# AudioMega_Oliver_v101.net
KiCad netlist of a schematic drawn in EAGLE
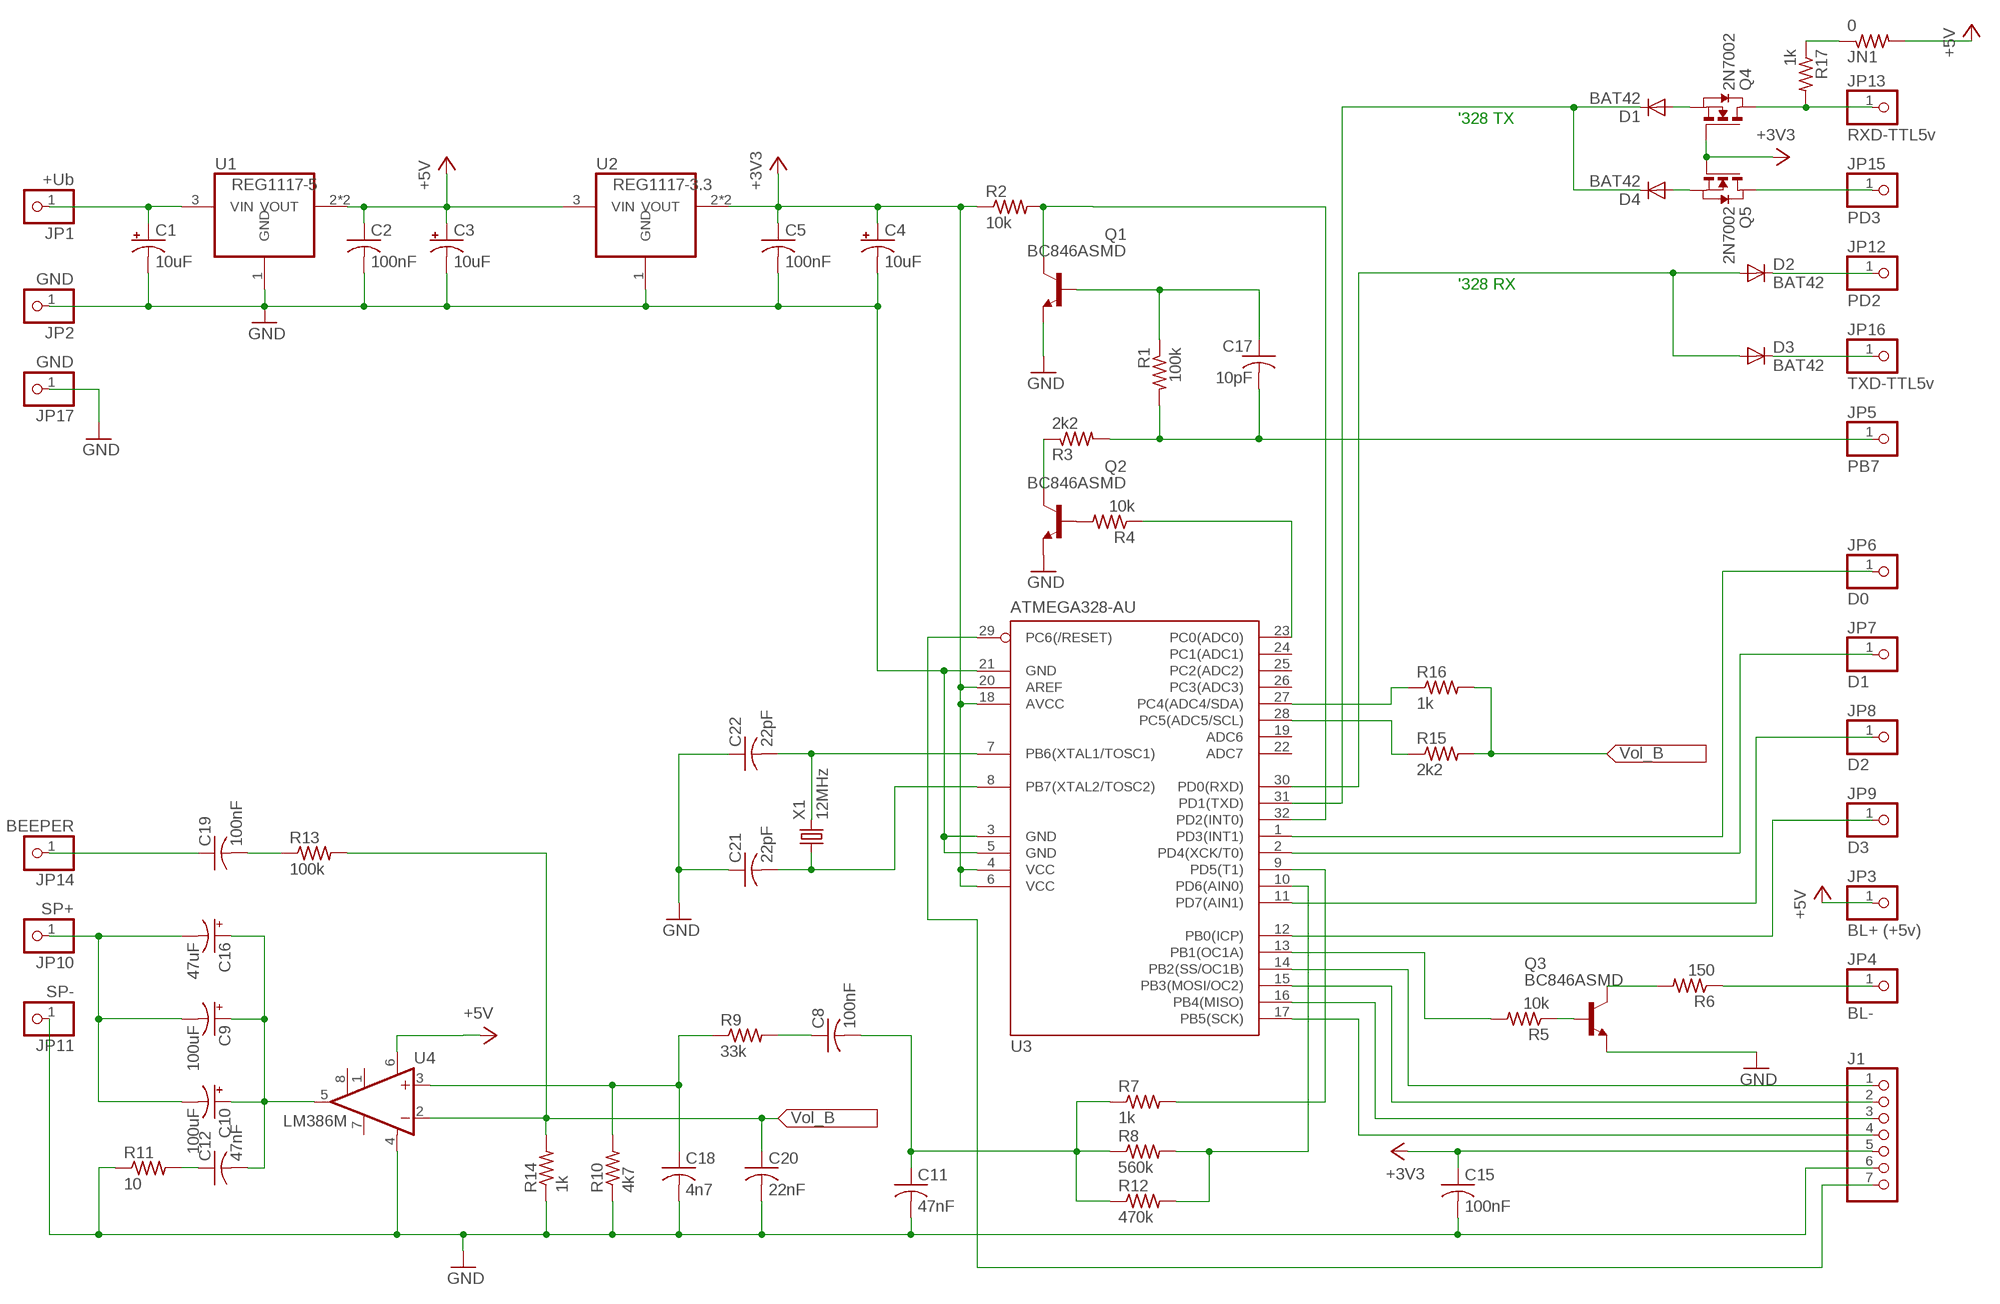
[diagram p0: schematic, sheet 1]

(export (version "E")
  (design (tool "Eeschema 10.0.6"))
  (components
    (comp (ref "C1")
      (value "10uF")
      (footprint "eagle-import:CT3528")
      (libsource (lib "eagle-import") (part "CPOL-USCT3528"))
    )
    (comp (ref "C2")
      (value "100nF")
      (footprint "eagle-import:C1206")
      (libsource (lib "eagle-import") (part "C-USC1206"))
    )
    (comp (ref "C3")
      (value "10uF")
      (footprint "eagle-import:CT3528")
      (libsource (lib "eagle-import") (part "CPOL-USCT3528"))
    )
    (comp (ref "C4")
      (value "10uF")
      (footprint "eagle-import:CT3528")
      (libsource (lib "eagle-import") (part "CPOL-USCT3528"))
    )
    (comp (ref "C5")
      (value "100nF")
      (footprint "eagle-import:C1206")
      (libsource (lib "eagle-import") (part "C-USC1206"))
    )
    (comp (ref "C8")
      (value "100nF")
      (footprint "eagle-import:C1206")
      (libsource (lib "eagle-import") (part "C-USC1206"))
    )
    (comp (ref "C9")
      (value "100uF")
      (footprint "eagle-import:CT6032")
      (libsource (lib "eagle-import") (part "CPOL-USCT6032"))
    )
    (comp (ref "C10")
      (value "100uF")
      (footprint "eagle-import:CT6032")
      (libsource (lib "eagle-import") (part "CPOL-USCT6032"))
    )
    (comp (ref "C11")
      (value "47nF")
      (footprint "eagle-import:C1206")
      (libsource (lib "eagle-import") (part "C-USC1206"))
    )
    (comp (ref "C12")
      (value "47nF")
      (footprint "eagle-import:C1206")
      (libsource (lib "eagle-import") (part "C-USC1206"))
    )
    (comp (ref "C15")
      (value "100nF")
      (footprint "eagle-import:C1206")
      (libsource (lib "eagle-import") (part "C-USC1206"))
    )
    (comp (ref "C16")
      (value "47uF")
      (footprint "eagle-import:CT6032")
      (libsource (lib "eagle-import") (part "CPOL-USCT6032"))
    )
    (comp (ref "C17")
      (value "10pF")
      (footprint "eagle-import:C1206")
      (libsource (lib "eagle-import") (part "C-USC1206"))
    )
    (comp (ref "C18")
      (value "4n7")
      (footprint "eagle-import:C1206")
      (libsource (lib "eagle-import") (part "C-USC1206"))
    )
    (comp (ref "C19")
      (value "100nF")
      (footprint "eagle-import:C1206")
      (libsource (lib "eagle-import") (part "C-USC1206"))
    )
    (comp (ref "C20")
      (value "22nF")
      (footprint "eagle-import:C1206")
      (libsource (lib "eagle-import") (part "C-USC1206"))
    )
    (comp (ref "C21")
      (value "22pF")
      (footprint "eagle-import:C1206")
      (libsource (lib "eagle-import") (part "C-USC1206"))
    )
    (comp (ref "C22")
      (value "22pF")
      (footprint "eagle-import:C1206")
      (libsource (lib "eagle-import") (part "C-USC1206"))
    )
    (comp (ref "D1")
      (value "BAT42")
      (footprint "eagle-import:SOD123")
      (libsource (lib "eagle-import") (part "DIODE-SOD123"))
    )
    (comp (ref "D2")
      (value "BAT42")
      (footprint "eagle-import:SOD123")
      (libsource (lib "eagle-import") (part "DIODE-SOD123"))
    )
    (comp (ref "D3")
      (value "BAT42")
      (footprint "eagle-import:SOD123")
      (libsource (lib "eagle-import") (part "DIODE-SOD123"))
    )
    (comp (ref "D4")
      (value "BAT42")
      (footprint "eagle-import:SOD123")
      (libsource (lib "eagle-import") (part "DIODE-SOD123"))
    )
    (comp (ref "J1")
      (value "PINHD-1X7")
      (footprint "eagle-import:1X07")
      (libsource (lib "eagle-import") (part "PINHD-1X7"))
    )
    (comp (ref "JN1")
      (value "0")
      (footprint "eagle-import:R1206")
      (libsource (lib "eagle-import") (part "R-US_R1206"))
    )
    (comp (ref "JP1")
      (value "+Ub")
      (footprint "eagle-import:1X01")
      (libsource (lib "eagle-import") (part "PINHD-1X1"))
    )
    (comp (ref "JP2")
      (value "GND")
      (footprint "eagle-import:1X01")
      (libsource (lib "eagle-import") (part "PINHD-1X1"))
    )
    (comp (ref "JP3")
      (value "BL+ (+5v)")
      (footprint "eagle-import:1X01")
      (libsource (lib "eagle-import") (part "PINHD-1X1"))
    )
    (comp (ref "JP4")
      (value "BL-")
      (footprint "eagle-import:1X01")
      (libsource (lib "eagle-import") (part "PINHD-1X1"))
    )
    (comp (ref "JP5")
      (value "PB7")
      (footprint "eagle-import:1X01")
      (libsource (lib "eagle-import") (part "PINHD-1X1"))
    )
    (comp (ref "JP6")
      (value "D0")
      (footprint "eagle-import:1X01")
      (libsource (lib "eagle-import") (part "PINHD-1X1"))
    )
    (comp (ref "JP7")
      (value "D1")
      (footprint "eagle-import:1X01")
      (libsource (lib "eagle-import") (part "PINHD-1X1"))
    )
    (comp (ref "JP8")
      (value "D2")
      (footprint "eagle-import:1X01")
      (libsource (lib "eagle-import") (part "PINHD-1X1"))
    )
    (comp (ref "JP9")
      (value "D3")
      (footprint "eagle-import:1X01")
      (libsource (lib "eagle-import") (part "PINHD-1X1"))
    )
    (comp (ref "JP10")
      (value "SP+")
      (footprint "eagle-import:1X01")
      (libsource (lib "eagle-import") (part "PINHD-1X1"))
    )
    (comp (ref "JP11")
      (value "SP-")
      (footprint "eagle-import:1X01")
      (libsource (lib "eagle-import") (part "PINHD-1X1"))
    )
    (comp (ref "JP12")
      (value "PD2")
      (footprint "eagle-import:1X01")
      (libsource (lib "eagle-import") (part "PINHD-1X1"))
    )
    (comp (ref "JP13")
      (value "RXD-TTL5v")
      (footprint "eagle-import:1X01")
      (libsource (lib "eagle-import") (part "PINHD-1X1"))
    )
    (comp (ref "JP14")
      (value "BEEPER")
      (footprint "eagle-import:1X01")
      (libsource (lib "eagle-import") (part "PINHD-1X1"))
    )
    (comp (ref "JP15")
      (value "PD3")
      (footprint "eagle-import:1X01")
      (libsource (lib "eagle-import") (part "PINHD-1X1"))
    )
    (comp (ref "JP16")
      (value "TXD-TTL5v")
      (footprint "eagle-import:1X01")
      (libsource (lib "eagle-import") (part "PINHD-1X1"))
    )
    (comp (ref "JP17")
      (value "GND")
      (footprint "eagle-import:1X01")
      (libsource (lib "eagle-import") (part "PINHD-1X1"))
    )
    (comp (ref "Q1")
      (value "BC846ASMD")
      (footprint "eagle-import:SOT23")
      (libsource (lib "eagle-import") (part "BC846SMDA"))
    )
    (comp (ref "Q2")
      (value "BC846ASMD")
      (footprint "eagle-import:SOT23")
      (libsource (lib "eagle-import") (part "BC846SMDA"))
    )
    (comp (ref "Q3")
      (value "BC846ASMD")
      (footprint "eagle-import:SOT23")
      (libsource (lib "eagle-import") (part "BC846SMDA"))
    )
    (comp (ref "Q4")
      (value "2N7002")
      (footprint "eagle-import:SOT-23")
      (libsource (lib "eagle-import") (part "NMOSSOT23"))
    )
    (comp (ref "Q5")
      (value "2N7002")
      (footprint "eagle-import:SOT-23")
      (fields (field (name "OC_FARNELL") "unknown") (field (name "OC_NEWARK") "unknown"))
      (libsource (lib "eagle-import") (part "NMOSSOT23"))
    )
    (comp (ref "R1")
      (value "100k")
      (footprint "eagle-import:R1206")
      (libsource (lib "eagle-import") (part "R-US_R1206"))
    )
    (comp (ref "R2")
      (value "10k")
      (footprint "eagle-import:R1206")
      (libsource (lib "eagle-import") (part "R-US_R1206"))
    )
    (comp (ref "R3")
      (value "2k2")
      (footprint "eagle-import:R1206")
      (libsource (lib "eagle-import") (part "R-US_R1206"))
    )
    (comp (ref "R4")
      (value "10k")
      (footprint "eagle-import:R1206")
      (libsource (lib "eagle-import") (part "R-US_R1206"))
    )
    (comp (ref "R5")
      (value "10k")
      (footprint "eagle-import:R1206")
      (libsource (lib "eagle-import") (part "R-US_R1206"))
    )
    (comp (ref "R6")
      (value "150")
      (footprint "eagle-import:R1206")
      (libsource (lib "eagle-import") (part "R-US_R1206"))
    )
    (comp (ref "R7")
      (value "1k")
      (footprint "eagle-import:R1206")
      (libsource (lib "eagle-import") (part "R-US_R1206"))
    )
    (comp (ref "R8")
      (value "560k")
      (footprint "eagle-import:R1206")
      (libsource (lib "eagle-import") (part "R-US_R1206"))
    )
    (comp (ref "R9")
      (value "33k")
      (footprint "eagle-import:R1206")
      (libsource (lib "eagle-import") (part "R-US_R1206"))
    )
    (comp (ref "R10")
      (value "4k7")
      (footprint "eagle-import:R1206")
      (libsource (lib "eagle-import") (part "R-US_R1206"))
    )
    (comp (ref "R11")
      (value "10")
      (footprint "eagle-import:R1206")
      (libsource (lib "eagle-import") (part "R-US_R1206"))
    )
    (comp (ref "R12")
      (value "470k")
      (footprint "eagle-import:R1206")
      (libsource (lib "eagle-import") (part "R-US_R1206"))
    )
    (comp (ref "R13")
      (value "100k")
      (footprint "eagle-import:R1206")
      (libsource (lib "eagle-import") (part "R-US_R1206"))
    )
    (comp (ref "R14")
      (value "1k")
      (footprint "eagle-import:R1206")
      (libsource (lib "eagle-import") (part "R-US_R1206"))
    )
    (comp (ref "R15")
      (value "2k2")
      (footprint "eagle-import:R1206")
      (libsource (lib "eagle-import") (part "R-US_R1206"))
    )
    (comp (ref "R16")
      (value "1k")
      (footprint "eagle-import:R1206")
      (libsource (lib "eagle-import") (part "R-US_R1206"))
    )
    (comp (ref "R17")
      (value "1k")
      (footprint "eagle-import:R1206")
      (libsource (lib "eagle-import") (part "R-US_R1206"))
    )
    (comp (ref "U1")
      (value "REG1117-5")
      (footprint "eagle-import:SOT223")
      (fields (field (name "MPN") "REG1117"))
      (libsource (lib "eagle-import") (part "REG1117"))
    )
    (comp (ref "U2")
      (value "REG1117-3.3")
      (footprint "eagle-import:SOT223")
      (fields (field (name "MPN") "REG1117"))
      (libsource (lib "eagle-import") (part "REG1117"))
    )
    (comp (ref "U3")
      (value "ATMEGA328-AU")
      (footprint "eagle-import:TQFP32-08")
      (fields (field (name "MPN") "ATMEGA8-16AU"))
      (libsource (lib "eagle-import") (part "MEGA8-AI"))
    )
    (comp (ref "U4")
      (value "LM386M")
      (footprint "eagle-import:SO08")
      (libsource (lib "eagle-import") (part "LM386?-M1"))
    )
    (comp (ref "X1")
      (value "12MHz")
      (footprint "eagle-import:HC49UP")
      (libsource (lib "eagle-import") (part "CRYSTALHC49UP"))
    )
  )
  (nets
    (net (code "1") (name "+3V3") (class "Default")
      (node (ref "C15") (pin "1") (pinfunction "1_1") (pintype "passive"))
      (node (ref "C4") (pin "+") (pinfunction "+_+") (pintype "passive"))
      (node (ref "C5") (pin "1") (pinfunction "1_1") (pintype "passive"))
      (node (ref "J1") (pin "5") (pinfunction "5_5") (pintype "passive"))
      (node (ref "Q4") (pin "3") (pinfunction "G_3") (pintype "passive"))
      (node (ref "Q5") (pin "3") (pinfunction "G_3") (pintype "passive"))
      (node (ref "R2") (pin "1") (pinfunction "1_1") (pintype "passive"))
      (node (ref "U2") (pin "2") (pinfunction "VOUT_2") (pintype "output"))
      (node (ref "U2") (pin "4") (pinfunction "VOUT_4") (pintype "output"))
      (node (ref "U3") (pin "18") (pinfunction "AVCC_18") (pintype "power_in"))
      (node (ref "U3") (pin "20") (pinfunction "AREF_20") (pintype "passive"))
      (node (ref "U3") (pin "4") (pinfunction "VCC_4") (pintype "power_in"))
      (node (ref "U3") (pin "6") (pinfunction "VCC_6") (pintype "power_in"))
    )
    (net (code "2") (name "+5V") (class "Default")
      (node (ref "C2") (pin "1") (pinfunction "1_1") (pintype "passive"))
      (node (ref "C3") (pin "+") (pinfunction "+_+") (pintype "passive"))
      (node (ref "JN1") (pin "2") (pinfunction "2_2") (pintype "passive"))
      (node (ref "JP3") (pin "1") (pinfunction "1_1") (pintype "passive"))
      (node (ref "U1") (pin "2") (pinfunction "VOUT_2") (pintype "output"))
      (node (ref "U1") (pin "4") (pinfunction "VOUT_4") (pintype "output"))
      (node (ref "U2") (pin "3") (pinfunction "VIN_3") (pintype "input"))
      (node (ref "U4") (pin "6") (pinfunction "VS_6") (pintype "power_in"))
    )
    (net (code "3") (name "/VOL_B") (class "Default")
      (node (ref "C20") (pin "1") (pinfunction "1_1") (pintype "passive"))
      (node (ref "R13") (pin "2") (pinfunction "2_2") (pintype "passive"))
      (node (ref "R14") (pin "2") (pinfunction "2_2") (pintype "passive"))
      (node (ref "R15") (pin "2") (pinfunction "2_2") (pintype "passive"))
      (node (ref "R16") (pin "2") (pinfunction "2_2") (pintype "passive"))
      (node (ref "U4") (pin "2") (pinfunction "-IN_2") (pintype "input"))
    )
    (net (code "4") (name "GND") (class "Default")
      (node (ref "C1") (pin "-") (pinfunction "-_-") (pintype "passive"))
      (node (ref "C11") (pin "2") (pinfunction "2_2") (pintype "passive"))
      (node (ref "C15") (pin "2") (pinfunction "2_2") (pintype "passive"))
      (node (ref "C18") (pin "2") (pinfunction "2_2") (pintype "passive"))
      (node (ref "C2") (pin "2") (pinfunction "2_2") (pintype "passive"))
      (node (ref "C20") (pin "2") (pinfunction "2_2") (pintype "passive"))
      (node (ref "C21") (pin "1") (pinfunction "1_1") (pintype "passive"))
      (node (ref "C22") (pin "1") (pinfunction "1_1") (pintype "passive"))
      (node (ref "C3") (pin "-") (pinfunction "-_-") (pintype "passive"))
      (node (ref "C4") (pin "-") (pinfunction "-_-") (pintype "passive"))
      (node (ref "C5") (pin "2") (pinfunction "2_2") (pintype "passive"))
      (node (ref "J1") (pin "6") (pinfunction "6_6") (pintype "passive"))
      (node (ref "JP11") (pin "1") (pinfunction "1_1") (pintype "passive"))
      (node (ref "JP17") (pin "1") (pinfunction "1_1") (pintype "passive"))
      (node (ref "JP2") (pin "1") (pinfunction "1_1") (pintype "passive"))
      (node (ref "Q1") (pin "2") (pinfunction "E_2") (pintype "passive"))
      (node (ref "Q2") (pin "2") (pinfunction "E_2") (pintype "passive"))
      (node (ref "Q3") (pin "2") (pinfunction "E_2") (pintype "passive"))
      (node (ref "R10") (pin "1") (pinfunction "1_1") (pintype "passive"))
      (node (ref "R11") (pin "1") (pinfunction "1_1") (pintype "passive"))
      (node (ref "R14") (pin "1") (pinfunction "1_1") (pintype "passive"))
      (node (ref "U1") (pin "1") (pinfunction "GND_1") (pintype "power_in"))
      (node (ref "U2") (pin "1") (pinfunction "GND_1") (pintype "power_in"))
      (node (ref "U3") (pin "21") (pinfunction "GND_21") (pintype "power_in"))
      (node (ref "U3") (pin "3") (pinfunction "GND_3") (pintype "power_in"))
      (node (ref "U3") (pin "5") (pinfunction "GND_5") (pintype "power_in"))
      (node (ref "U4") (pin "4") (pinfunction "GND_4") (pintype "power_in"))
    )
    (net (code "5") (name "Net-(C8-Pad1)") (class "Default")
      (node (ref "C8") (pin "1") (pinfunction "1_1") (pintype "passive"))
      (node (ref "R9") (pin "2") (pinfunction "2_2") (pintype "passive"))
    )
    (net (code "6") (name "Net-(C10-Pad-)") (class "Default")
      (node (ref "C10") (pin "-") (pinfunction "-_-") (pintype "passive"))
      (node (ref "C16") (pin "-") (pinfunction "-_-") (pintype "passive"))
      (node (ref "C9") (pin "-") (pinfunction "-_-") (pintype "passive"))
      (node (ref "JP10") (pin "1") (pinfunction "1_1") (pintype "passive"))
    )
    (net (code "7") (name "Net-(C11-Pad1)") (class "Default")
      (node (ref "C11") (pin "1") (pinfunction "1_1") (pintype "passive"))
      (node (ref "C8") (pin "2") (pinfunction "2_2") (pintype "passive"))
      (node (ref "R12") (pin "1") (pinfunction "1_1") (pintype "passive"))
      (node (ref "R7") (pin "1") (pinfunction "1_1") (pintype "passive"))
      (node (ref "R8") (pin "1") (pinfunction "1_1") (pintype "passive"))
    )
    (net (code "8") (name "Net-(C12-Pad1)") (class "Default")
      (node (ref "C12") (pin "1") (pinfunction "1_1") (pintype "passive"))
      (node (ref "R11") (pin "2") (pinfunction "2_2") (pintype "passive"))
    )
    (net (code "9") (name "Net-(C17-Pad2)") (class "Default")
      (node (ref "C17") (pin "2") (pinfunction "2_2") (pintype "passive"))
      (node (ref "JP5") (pin "1") (pinfunction "1_1") (pintype "passive"))
      (node (ref "R1") (pin "2") (pinfunction "2_2") (pintype "passive"))
      (node (ref "R3") (pin "2") (pinfunction "2_2") (pintype "passive"))
    )
    (net (code "10") (name "Net-(C19-Pad1)") (class "Default")
      (node (ref "C19") (pin "1") (pinfunction "1_1") (pintype "passive"))
      (node (ref "JP14") (pin "1") (pinfunction "1_1") (pintype "passive"))
    )
    (net (code "11") (name "Net-(C19-Pad2)") (class "Default")
      (node (ref "C19") (pin "2") (pinfunction "2_2") (pintype "passive"))
      (node (ref "R13") (pin "1") (pinfunction "1_1") (pintype "passive"))
    )
    (net (code "12") (name "Net-(D2-PadC)") (class "Default")
      (node (ref "D2") (pin "C") (pinfunction "C_C") (pintype "passive"))
      (node (ref "JP12") (pin "1") (pinfunction "1_1") (pintype "passive"))
    )
    (net (code "13") (name "Net-(D3-PadC)") (class "Default")
      (node (ref "D3") (pin "C") (pinfunction "C_C") (pintype "passive"))
      (node (ref "JP16") (pin "1") (pinfunction "1_1") (pintype "passive"))
    )
    (net (code "14") (name "Net-(JN1-Pad1)") (class "Default")
      (node (ref "JN1") (pin "1") (pinfunction "1_1") (pintype "passive"))
      (node (ref "R17") (pin "1") (pinfunction "1_1") (pintype "passive"))
    )
    (net (code "15") (name "Net-(JP4-Pad1)") (class "Default")
      (node (ref "JP4") (pin "1") (pinfunction "1_1") (pintype "passive"))
      (node (ref "R6") (pin "1") (pinfunction "1_1") (pintype "passive"))
    )
    (net (code "16") (name "Net-(Q1-B)") (class "Default")
      (node (ref "C17") (pin "1") (pinfunction "1_1") (pintype "passive"))
      (node (ref "Q1") (pin "1") (pinfunction "B_1") (pintype "passive"))
      (node (ref "R1") (pin "1") (pinfunction "1_1") (pintype "passive"))
    )
    (net (code "17") (name "Net-(Q1-C)") (class "Default")
      (node (ref "Q1") (pin "3") (pinfunction "C_3") (pintype "passive"))
      (node (ref "R2") (pin "2") (pinfunction "2_2") (pintype "passive"))
      (node (ref "U3") (pin "32") (pinfunction "PD2(INT0)_32") (pintype "bidirectional"))
    )
    (net (code "18") (name "Net-(Q2-B)") (class "Default")
      (node (ref "Q2") (pin "1") (pinfunction "B_1") (pintype "passive"))
      (node (ref "R4") (pin "2") (pinfunction "2_2") (pintype "passive"))
    )
    (net (code "19") (name "Net-(Q2-C)") (class "Default")
      (node (ref "Q2") (pin "3") (pinfunction "C_3") (pintype "passive"))
      (node (ref "R3") (pin "1") (pinfunction "1_1") (pintype "passive"))
    )
    (net (code "20") (name "Net-(Q3-B)") (class "Default")
      (node (ref "Q3") (pin "1") (pinfunction "B_1") (pintype "passive"))
      (node (ref "R5") (pin "1") (pinfunction "1_1") (pintype "passive"))
    )
    (net (code "21") (name "Net-(Q3-C)") (class "Default")
      (node (ref "Q3") (pin "3") (pinfunction "C_3") (pintype "passive"))
      (node (ref "R6") (pin "2") (pinfunction "2_2") (pintype "passive"))
    )
    (net (code "22") (name "Net-(Q4-D)") (class "Default")
      (node (ref "JP13") (pin "1") (pinfunction "1_1") (pintype "passive"))
      (node (ref "Q4") (pin "1") (pinfunction "D_1") (pintype "passive"))
      (node (ref "R17") (pin "2") (pinfunction "2_2") (pintype "passive"))
    )
    (net (code "23") (name "Net-(Q4-S)") (class "Default")
      (node (ref "D1") (pin "A") (pinfunction "A_A") (pintype "passive"))
      (node (ref "Q4") (pin "2") (pinfunction "S_2") (pintype "passive"))
    )
    (net (code "24") (name "Net-(Q5-D)") (class "Default")
      (node (ref "JP15") (pin "1") (pinfunction "1_1") (pintype "passive"))
      (node (ref "Q5") (pin "1") (pinfunction "D_1") (pintype "passive"))
    )
    (net (code "25") (name "Net-(Q5-S)") (class "Default")
      (node (ref "D4") (pin "A") (pinfunction "A_A") (pintype "passive"))
      (node (ref "Q5") (pin "2") (pinfunction "S_2") (pintype "passive"))
    )
    (net (code "26") (name "Net-(U1-VIN)") (class "Default")
      (node (ref "C1") (pin "+") (pinfunction "+_+") (pintype "passive"))
      (node (ref "JP1") (pin "1") (pinfunction "1_1") (pintype "passive"))
      (node (ref "U1") (pin "3") (pinfunction "VIN_3") (pintype "input"))
    )
    (net (code "27") (name "Net-(U3-PB0(ICP))") (class "Default")
      (node (ref "JP9") (pin "1") (pinfunction "1_1") (pintype "passive"))
      (node (ref "U3") (pin "12") (pinfunction "PB0(ICP)_12") (pintype "bidirectional"))
    )
    (net (code "28") (name "Net-(U3-PB1(OC1A))") (class "Default")
      (node (ref "R5") (pin "2") (pinfunction "2_2") (pintype "passive"))
      (node (ref "U3") (pin "13") (pinfunction "PB1(OC1A)_13") (pintype "bidirectional"))
    )
    (net (code "29") (name "Net-(U3-PB2(SS{slash}OC1B))") (class "Default")
      (node (ref "J1") (pin "1") (pinfunction "1_1") (pintype "passive"))
      (node (ref "U3") (pin "14") (pinfunction "PB2(SS/OC1B)_14") (pintype "bidirectional"))
    )
    (net (code "30") (name "Net-(U3-PB3(MOSI{slash}OC2))") (class "Default")
      (node (ref "J1") (pin "2") (pinfunction "2_2") (pintype "passive"))
      (node (ref "U3") (pin "15") (pinfunction "PB3(MOSI/OC2)_15") (pintype "bidirectional"))
    )
    (net (code "31") (name "Net-(U3-PB4(MISO))") (class "Default")
      (node (ref "J1") (pin "3") (pinfunction "3_3") (pintype "passive"))
      (node (ref "U3") (pin "16") (pinfunction "PB4(MISO)_16") (pintype "bidirectional"))
    )
    (net (code "32") (name "Net-(U3-PB5(SCK))") (class "Default")
      (node (ref "J1") (pin "4") (pinfunction "4_4") (pintype "passive"))
      (node (ref "U3") (pin "17") (pinfunction "PB5(SCK)_17") (pintype "bidirectional"))
    )
    (net (code "33") (name "Net-(U3-PB6(XTAL1{slash}TOSC1))") (class "Default")
      (node (ref "C22") (pin "2") (pinfunction "2_2") (pintype "passive"))
      (node (ref "U3") (pin "7") (pinfunction "PB6(XTAL1/TOSC1)_7") (pintype "bidirectional"))
      (node (ref "X1") (pin "2") (pinfunction "2_2") (pintype "passive"))
    )
    (net (code "34") (name "Net-(U3-PB7(XTAL2{slash}TOSC2))") (class "Default")
      (node (ref "C21") (pin "2") (pinfunction "2_2") (pintype "passive"))
      (node (ref "U3") (pin "8") (pinfunction "PB7(XTAL2/TOSC2)_8") (pintype "bidirectional"))
      (node (ref "X1") (pin "1") (pinfunction "1_1") (pintype "passive"))
    )
    (net (code "35") (name "Net-(U3-PC0(ADC0))") (class "Default")
      (node (ref "R4") (pin "1") (pinfunction "1_1") (pintype "passive"))
      (node (ref "U3") (pin "23") (pinfunction "PC0(ADC0)_23") (pintype "bidirectional"))
    )
    (net (code "36") (name "Net-(U3-PC4(ADC4{slash}SDA))") (class "Default")
      (node (ref "R16") (pin "1") (pinfunction "1_1") (pintype "passive"))
      (node (ref "U3") (pin "27") (pinfunction "PC4(ADC4/SDA)_27") (pintype "bidirectional"))
    )
    (net (code "37") (name "Net-(U3-PC5(ADC5{slash}SCL))") (class "Default")
      (node (ref "R15") (pin "1") (pinfunction "1_1") (pintype "passive"))
      (node (ref "U3") (pin "28") (pinfunction "PC5(ADC5/SCL)_28") (pintype "bidirectional"))
    )
    (net (code "38") (name "Net-(U3-PC6({slash}RESET))") (class "Default")
      (node (ref "J1") (pin "7") (pinfunction "7_7") (pintype "passive"))
      (node (ref "U3") (pin "29") (pinfunction "PC6(/RESET)_29") (pintype "bidirectional"))
    )
    (net (code "39") (name "Net-(U3-PD0(RXD))") (class "Default")
      (node (ref "D2") (pin "A") (pinfunction "A_A") (pintype "passive"))
      (node (ref "D3") (pin "A") (pinfunction "A_A") (pintype "passive"))
      (node (ref "U3") (pin "30") (pinfunction "PD0(RXD)_30") (pintype "bidirectional"))
    )
    (net (code "40") (name "Net-(U3-PD1(TXD))") (class "Default")
      (node (ref "D1") (pin "C") (pinfunction "C_C") (pintype "passive"))
      (node (ref "D4") (pin "C") (pinfunction "C_C") (pintype "passive"))
      (node (ref "U3") (pin "31") (pinfunction "PD1(TXD)_31") (pintype "bidirectional"))
    )
    (net (code "41") (name "Net-(U3-PD3(INT1))") (class "Default")
      (node (ref "JP6") (pin "1") (pinfunction "1_1") (pintype "passive"))
      (node (ref "U3") (pin "1") (pinfunction "PD3(INT1)_1") (pintype "bidirectional"))
    )
    (net (code "42") (name "Net-(U3-PD4(XCK{slash}T0))") (class "Default")
      (node (ref "JP7") (pin "1") (pinfunction "1_1") (pintype "passive"))
      (node (ref "U3") (pin "2") (pinfunction "PD4(XCK/T0)_2") (pintype "bidirectional"))
    )
    (net (code "43") (name "Net-(U3-PD5(T1))") (class "Default")
      (node (ref "R7") (pin "2") (pinfunction "2_2") (pintype "passive"))
      (node (ref "U3") (pin "9") (pinfunction "PD5(T1)_9") (pintype "bidirectional"))
    )
    (net (code "44") (name "Net-(U3-PD6(AIN0))") (class "Default")
      (node (ref "R12") (pin "2") (pinfunction "2_2") (pintype "passive"))
      (node (ref "R8") (pin "2") (pinfunction "2_2") (pintype "passive"))
      (node (ref "U3") (pin "10") (pinfunction "PD6(AIN0)_10") (pintype "bidirectional"))
    )
    (net (code "45") (name "Net-(U3-PD7(AIN1))") (class "Default")
      (node (ref "JP8") (pin "1") (pinfunction "1_1") (pintype "passive"))
      (node (ref "U3") (pin "11") (pinfunction "PD7(AIN1)_11") (pintype "bidirectional"))
    )
    (net (code "46") (name "Net-(U4-+IN)") (class "Default")
      (node (ref "C18") (pin "1") (pinfunction "1_1") (pintype "passive"))
      (node (ref "R10") (pin "2") (pinfunction "2_2") (pintype "passive"))
      (node (ref "R9") (pin "1") (pinfunction "1_1") (pintype "passive"))
      (node (ref "U4") (pin "3") (pinfunction "+IN_3") (pintype "input"))
    )
    (net (code "47") (name "Net-(U4-OUT)") (class "Default")
      (node (ref "C10") (pin "+") (pinfunction "+_+") (pintype "passive"))
      (node (ref "C12") (pin "2") (pinfunction "2_2") (pintype "passive"))
      (node (ref "C16") (pin "+") (pinfunction "+_+") (pintype "passive"))
      (node (ref "C9") (pin "+") (pinfunction "+_+") (pintype "passive"))
      (node (ref "U4") (pin "5") (pinfunction "OUT_5") (pintype "output"))
    )
    (net (code "48") (name "unconnected-(U3-ADC6-Pad19)") (class "Default")
      (node (ref "U3") (pin "19") (pinfunction "ADC6_19") (pintype "bidirectional"))
    )
    (net (code "49") (name "unconnected-(U3-ADC7-Pad22)") (class "Default")
      (node (ref "U3") (pin "22") (pinfunction "ADC7_22") (pintype "bidirectional"))
    )
    (net (code "50") (name "unconnected-(U3-PC1(ADC1)-Pad24)") (class "Default")
      (node (ref "U3") (pin "24") (pinfunction "PC1(ADC1)_24") (pintype "bidirectional"))
    )
    (net (code "51") (name "unconnected-(U3-PC2(ADC2)-Pad25)") (class "Default")
      (node (ref "U3") (pin "25") (pinfunction "PC2(ADC2)_25") (pintype "bidirectional"))
    )
    (net (code "52") (name "unconnected-(U3-PC3(ADC3)-Pad26)") (class "Default")
      (node (ref "U3") (pin "26") (pinfunction "PC3(ADC3)_26") (pintype "bidirectional"))
    )
    (net (code "53") (name "unconnected-(U4-BYPASS-Pad7)") (class "Default")
      (node (ref "U4") (pin "7") (pinfunction "BYPASS_7") (pintype "passive"))
    )
    (net (code "54") (name "unconnected-(U4-GAIN-Pad1)") (class "Default")
      (node (ref "U4") (pin "1") (pinfunction "GAIN_1") (pintype "passive"))
    )
    (net (code "55") (name "unconnected-(U4-GAIN-Pad8)") (class "Default")
      (node (ref "U4") (pin "8") (pinfunction "GAIN_8") (pintype "passive"))
    )
  )
)
